# In_Out.net
KiCad netlist of a schematic drawn in Altium Designer
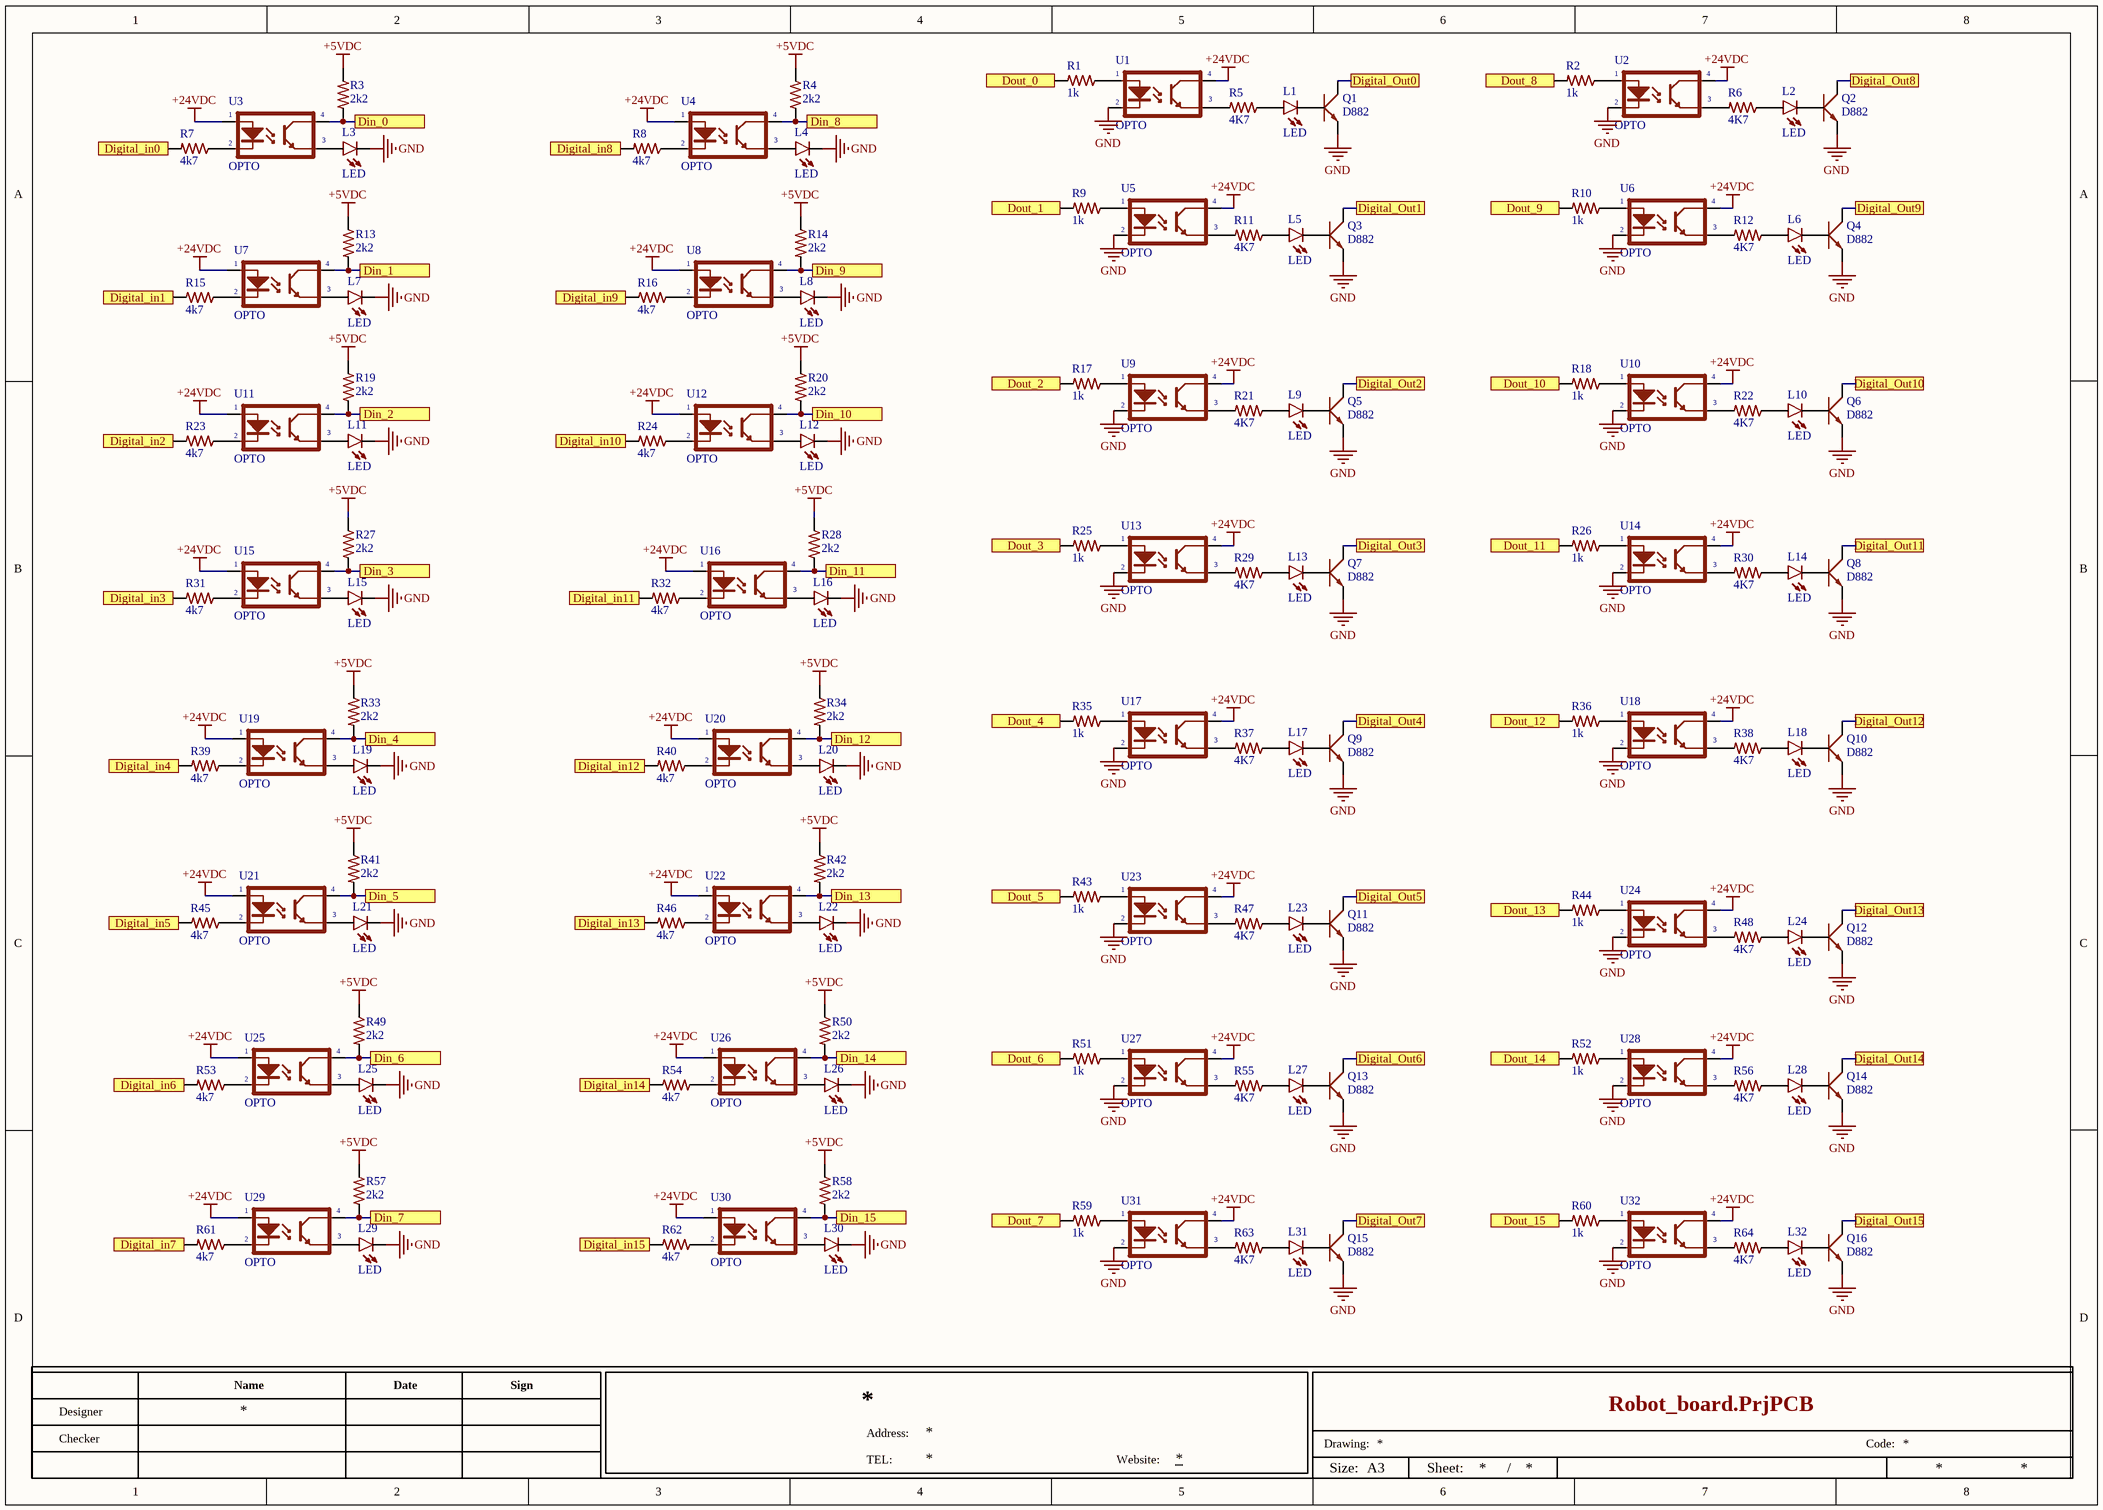
[diagram p0: In_Out.SchDoc]

(export (version "E")
  (design (tool "Eeschema 10.0.6"))
  (components
    (comp (ref "L1")
      (value "LED")
      (footprint "LED_GREEN_SMD_0603")
      (description "Lighting Eminter Diode")
      (libsource (lib "UzumakiIchiro_Library") (part "LED"))
    )
    (comp (ref "L2")
      (value "LED")
      (footprint "LED_GREEN_SMD_0603")
      (description "Lighting Eminter Diode")
      (libsource (lib "UzumakiIchiro_Library") (part "LED"))
    )
    (comp (ref "L3")
      (value "LED")
      (footprint "LED_RED_SMD_0603")
      (description "Lighting Eminter Diode")
      (libsource (lib "UzumakiIchiro_Library") (part "LED"))
    )
    (comp (ref "L4")
      (value "LED")
      (footprint "LED_RED_SMD_0603")
      (description "Lighting Eminter Diode")
      (libsource (lib "UzumakiIchiro_Library") (part "LED"))
    )
    (comp (ref "L5")
      (value "LED")
      (footprint "LED_GREEN_SMD_0603")
      (description "Lighting Eminter Diode")
      (libsource (lib "UzumakiIchiro_Library") (part "LED"))
    )
    (comp (ref "L6")
      (value "LED")
      (footprint "LED_GREEN_SMD_0603")
      (description "Lighting Eminter Diode")
      (libsource (lib "UzumakiIchiro_Library") (part "LED"))
    )
    (comp (ref "L7")
      (value "LED")
      (footprint "LED_RED_SMD_0603")
      (description "Lighting Eminter Diode")
      (libsource (lib "UzumakiIchiro_Library") (part "LED"))
    )
    (comp (ref "L8")
      (value "LED")
      (footprint "LED_RED_SMD_0603")
      (description "Lighting Eminter Diode")
      (libsource (lib "UzumakiIchiro_Library") (part "LED"))
    )
    (comp (ref "L9")
      (value "LED")
      (footprint "LED_GREEN_SMD_0603")
      (description "Lighting Eminter Diode")
      (libsource (lib "UzumakiIchiro_Library") (part "LED"))
    )
    (comp (ref "L10")
      (value "LED")
      (footprint "LED_GREEN_SMD_0603")
      (description "Lighting Eminter Diode")
      (libsource (lib "UzumakiIchiro_Library") (part "LED"))
    )
    (comp (ref "L11")
      (value "LED")
      (footprint "LED_RED_SMD_0603")
      (description "Lighting Eminter Diode")
      (libsource (lib "UzumakiIchiro_Library") (part "LED"))
    )
    (comp (ref "L12")
      (value "LED")
      (footprint "LED_RED_SMD_0603")
      (description "Lighting Eminter Diode")
      (libsource (lib "UzumakiIchiro_Library") (part "LED"))
    )
    (comp (ref "L13")
      (value "LED")
      (footprint "LED_GREEN_SMD_0603")
      (description "Lighting Eminter Diode")
      (libsource (lib "UzumakiIchiro_Library") (part "LED"))
    )
    (comp (ref "L14")
      (value "LED")
      (footprint "LED_GREEN_SMD_0603")
      (description "Lighting Eminter Diode")
      (libsource (lib "UzumakiIchiro_Library") (part "LED"))
    )
    (comp (ref "L15")
      (value "LED")
      (footprint "LED_RED_SMD_0603")
      (description "Lighting Eminter Diode")
      (libsource (lib "UzumakiIchiro_Library") (part "LED"))
    )
    (comp (ref "L16")
      (value "LED")
      (footprint "LED_RED_SMD_0603")
      (description "Lighting Eminter Diode")
      (libsource (lib "UzumakiIchiro_Library") (part "LED"))
    )
    (comp (ref "L17")
      (value "LED")
      (footprint "LED_GREEN_SMD_0603")
      (description "Lighting Eminter Diode")
      (libsource (lib "UzumakiIchiro_Library") (part "LED"))
    )
    (comp (ref "L18")
      (value "LED")
      (footprint "LED_GREEN_SMD_0603")
      (description "Lighting Eminter Diode")
      (libsource (lib "UzumakiIchiro_Library") (part "LED"))
    )
    (comp (ref "L19")
      (value "LED")
      (footprint "LED_RED_SMD_0603")
      (description "Lighting Eminter Diode")
      (libsource (lib "UzumakiIchiro_Library") (part "LED"))
    )
    (comp (ref "L20")
      (value "LED")
      (footprint "LED_RED_SMD_0603")
      (description "Lighting Eminter Diode")
      (libsource (lib "UzumakiIchiro_Library") (part "LED"))
    )
    (comp (ref "L21")
      (value "LED")
      (footprint "LED_RED_SMD_0603")
      (description "Lighting Eminter Diode")
      (libsource (lib "UzumakiIchiro_Library") (part "LED"))
    )
    (comp (ref "L22")
      (value "LED")
      (footprint "LED_RED_SMD_0603")
      (description "Lighting Eminter Diode")
      (libsource (lib "UzumakiIchiro_Library") (part "LED"))
    )
    (comp (ref "L23")
      (value "LED")
      (footprint "LED_GREEN_SMD_0603")
      (description "Lighting Eminter Diode")
      (libsource (lib "UzumakiIchiro_Library") (part "LED"))
    )
    (comp (ref "L24")
      (value "LED")
      (footprint "LED_GREEN_SMD_0603")
      (description "Lighting Eminter Diode")
      (libsource (lib "UzumakiIchiro_Library") (part "LED"))
    )
    (comp (ref "L25")
      (value "LED")
      (footprint "LED_RED_SMD_0603")
      (description "Lighting Eminter Diode")
      (libsource (lib "UzumakiIchiro_Library") (part "LED"))
    )
    (comp (ref "L26")
      (value "LED")
      (footprint "LED_RED_SMD_0603")
      (description "Lighting Eminter Diode")
      (libsource (lib "UzumakiIchiro_Library") (part "LED"))
    )
    (comp (ref "L27")
      (value "LED")
      (footprint "LED_GREEN_SMD_0603")
      (description "Lighting Eminter Diode")
      (libsource (lib "UzumakiIchiro_Library") (part "LED"))
    )
    (comp (ref "L28")
      (value "LED")
      (footprint "LED_GREEN_SMD_0603")
      (description "Lighting Eminter Diode")
      (libsource (lib "UzumakiIchiro_Library") (part "LED"))
    )
    (comp (ref "L29")
      (value "LED")
      (footprint "LED_RED_SMD_0603")
      (description "Lighting Eminter Diode")
      (libsource (lib "UzumakiIchiro_Library") (part "LED"))
    )
    (comp (ref "L30")
      (value "LED")
      (footprint "LED_RED_SMD_0603")
      (description "Lighting Eminter Diode")
      (libsource (lib "UzumakiIchiro_Library") (part "LED"))
    )
    (comp (ref "L31")
      (value "LED")
      (footprint "LED_GREEN_SMD_0603")
      (description "Lighting Eminter Diode")
      (libsource (lib "UzumakiIchiro_Library") (part "LED"))
    )
    (comp (ref "L32")
      (value "LED")
      (footprint "LED_GREEN_SMD_0603")
      (description "Lighting Eminter Diode")
      (libsource (lib "UzumakiIchiro_Library") (part "LED"))
    )
    (comp (ref "Q1")
      (value "D882")
      (footprint "SOT89")
      (libsource (lib "UzumakiIchiro_Library") (part "Tranzitor NPN"))
    )
    (comp (ref "Q2")
      (value "D882")
      (footprint "SOT89")
      (libsource (lib "UzumakiIchiro_Library") (part "Tranzitor NPN"))
    )
    (comp (ref "Q3")
      (value "D882")
      (footprint "SOT89")
      (libsource (lib "UzumakiIchiro_Library") (part "Tranzitor NPN"))
    )
    (comp (ref "Q4")
      (value "D882")
      (footprint "SOT89")
      (libsource (lib "UzumakiIchiro_Library") (part "Tranzitor NPN"))
    )
    (comp (ref "Q5")
      (value "D882")
      (footprint "SOT89")
      (libsource (lib "UzumakiIchiro_Library") (part "Tranzitor NPN"))
    )
    (comp (ref "Q6")
      (value "D882")
      (footprint "SOT89")
      (libsource (lib "UzumakiIchiro_Library") (part "Tranzitor NPN"))
    )
    (comp (ref "Q7")
      (value "D882")
      (footprint "SOT89")
      (libsource (lib "UzumakiIchiro_Library") (part "Tranzitor NPN"))
    )
    (comp (ref "Q8")
      (value "D882")
      (footprint "SOT89")
      (libsource (lib "UzumakiIchiro_Library") (part "Tranzitor NPN"))
    )
    (comp (ref "Q9")
      (value "D882")
      (footprint "SOT89")
      (libsource (lib "UzumakiIchiro_Library") (part "Tranzitor NPN"))
    )
    (comp (ref "Q10")
      (value "D882")
      (footprint "SOT89")
      (libsource (lib "UzumakiIchiro_Library") (part "Tranzitor NPN"))
    )
    (comp (ref "Q11")
      (value "D882")
      (footprint "SOT89")
      (libsource (lib "UzumakiIchiro_Library") (part "Tranzitor NPN"))
    )
    (comp (ref "Q12")
      (value "D882")
      (footprint "SOT89")
      (libsource (lib "UzumakiIchiro_Library") (part "Tranzitor NPN"))
    )
    (comp (ref "Q13")
      (value "D882")
      (footprint "SOT89")
      (libsource (lib "UzumakiIchiro_Library") (part "Tranzitor NPN"))
    )
    (comp (ref "Q14")
      (value "D882")
      (footprint "SOT89")
      (libsource (lib "UzumakiIchiro_Library") (part "Tranzitor NPN"))
    )
    (comp (ref "Q15")
      (value "D882")
      (footprint "SOT89")
      (libsource (lib "UzumakiIchiro_Library") (part "Tranzitor NPN"))
    )
    (comp (ref "Q16")
      (value "D882")
      (footprint "SOT89")
      (libsource (lib "UzumakiIchiro_Library") (part "Tranzitor NPN"))
    )
    (comp (ref "R1")
      (value "1k")
      (footprint "RES_SMD0603")
      (libsource (lib "UzumakiIchiro_Library") (part "Resistor"))
    )
    (comp (ref "R2")
      (value "1k")
      (footprint "RES_SMD0603")
      (libsource (lib "UzumakiIchiro_Library") (part "Resistor"))
    )
    (comp (ref "R3")
      (value "2k2")
      (footprint "RES_SMD0603")
      (libsource (lib "UzumakiIchiro_Library") (part "Resistor"))
    )
    (comp (ref "R4")
      (value "2k2")
      (footprint "RES_SMD0603")
      (libsource (lib "UzumakiIchiro_Library") (part "Resistor"))
    )
    (comp (ref "R5")
      (value "4K7")
      (footprint "RES_SMD0603")
      (libsource (lib "UzumakiIchiro_Library") (part "Resistor"))
    )
    (comp (ref "R6")
      (value "4K7")
      (footprint "RES_SMD0603")
      (libsource (lib "UzumakiIchiro_Library") (part "Resistor"))
    )
    (comp (ref "R7")
      (value "4k7")
      (footprint "RES_SMD0603")
      (libsource (lib "UzumakiIchiro_Library") (part "Resistor"))
    )
    (comp (ref "R8")
      (value "4k7")
      (footprint "RES_SMD0603")
      (libsource (lib "UzumakiIchiro_Library") (part "Resistor"))
    )
    (comp (ref "R9")
      (value "1k")
      (footprint "RES_SMD0603")
      (libsource (lib "UzumakiIchiro_Library") (part "Resistor"))
    )
    (comp (ref "R10")
      (value "1k")
      (footprint "RES_SMD0603")
      (libsource (lib "UzumakiIchiro_Library") (part "Resistor"))
    )
    (comp (ref "R11")
      (value "4K7")
      (footprint "RES_SMD0603")
      (libsource (lib "UzumakiIchiro_Library") (part "Resistor"))
    )
    (comp (ref "R12")
      (value "4K7")
      (footprint "RES_SMD0603")
      (libsource (lib "UzumakiIchiro_Library") (part "Resistor"))
    )
    (comp (ref "R13")
      (value "2k2")
      (footprint "RES_SMD0603")
      (libsource (lib "UzumakiIchiro_Library") (part "Resistor"))
    )
    (comp (ref "R14")
      (value "2k2")
      (footprint "RES_SMD0603")
      (libsource (lib "UzumakiIchiro_Library") (part "Resistor"))
    )
    (comp (ref "R15")
      (value "4k7")
      (footprint "RES_SMD0603")
      (libsource (lib "UzumakiIchiro_Library") (part "Resistor"))
    )
    (comp (ref "R16")
      (value "4k7")
      (footprint "RES_SMD0603")
      (libsource (lib "UzumakiIchiro_Library") (part "Resistor"))
    )
    (comp (ref "R17")
      (value "1k")
      (footprint "RES_SMD0603")
      (libsource (lib "UzumakiIchiro_Library") (part "Resistor"))
    )
    (comp (ref "R18")
      (value "1k")
      (footprint "RES_SMD0603")
      (libsource (lib "UzumakiIchiro_Library") (part "Resistor"))
    )
    (comp (ref "R19")
      (value "2k2")
      (footprint "RES_SMD0603")
      (libsource (lib "UzumakiIchiro_Library") (part "Resistor"))
    )
    (comp (ref "R20")
      (value "2k2")
      (footprint "RES_SMD0603")
      (libsource (lib "UzumakiIchiro_Library") (part "Resistor"))
    )
    (comp (ref "R21")
      (value "4K7")
      (footprint "RES_SMD0603")
      (libsource (lib "UzumakiIchiro_Library") (part "Resistor"))
    )
    (comp (ref "R22")
      (value "4K7")
      (footprint "RES_SMD0603")
      (libsource (lib "UzumakiIchiro_Library") (part "Resistor"))
    )
    (comp (ref "R23")
      (value "4k7")
      (footprint "RES_SMD0603")
      (libsource (lib "UzumakiIchiro_Library") (part "Resistor"))
    )
    (comp (ref "R24")
      (value "4k7")
      (footprint "RES_SMD0603")
      (libsource (lib "UzumakiIchiro_Library") (part "Resistor"))
    )
    (comp (ref "R25")
      (value "1k")
      (footprint "RES_SMD0603")
      (libsource (lib "UzumakiIchiro_Library") (part "Resistor"))
    )
    (comp (ref "R26")
      (value "1k")
      (footprint "RES_SMD0603")
      (libsource (lib "UzumakiIchiro_Library") (part "Resistor"))
    )
    (comp (ref "R27")
      (value "2k2")
      (footprint "RES_SMD0603")
      (libsource (lib "UzumakiIchiro_Library") (part "Resistor"))
    )
    (comp (ref "R28")
      (value "2k2")
      (footprint "RES_SMD0603")
      (libsource (lib "UzumakiIchiro_Library") (part "Resistor"))
    )
    (comp (ref "R29")
      (value "4K7")
      (footprint "RES_SMD0603")
      (libsource (lib "UzumakiIchiro_Library") (part "Resistor"))
    )
    (comp (ref "R30")
      (value "4K7")
      (footprint "RES_SMD0603")
      (libsource (lib "UzumakiIchiro_Library") (part "Resistor"))
    )
    (comp (ref "R31")
      (value "4k7")
      (footprint "RES_SMD0603")
      (libsource (lib "UzumakiIchiro_Library") (part "Resistor"))
    )
    (comp (ref "R32")
      (value "4k7")
      (footprint "RES_SMD0603")
      (libsource (lib "UzumakiIchiro_Library") (part "Resistor"))
    )
    (comp (ref "R33")
      (value "2k2")
      (footprint "RES_SMD0603")
      (libsource (lib "UzumakiIchiro_Library") (part "Resistor"))
    )
    (comp (ref "R34")
      (value "2k2")
      (footprint "RES_SMD0603")
      (libsource (lib "UzumakiIchiro_Library") (part "Resistor"))
    )
    (comp (ref "R35")
      (value "1k")
      (footprint "RES_SMD0603")
      (libsource (lib "UzumakiIchiro_Library") (part "Resistor"))
    )
    (comp (ref "R36")
      (value "1k")
      (footprint "RES_SMD0603")
      (libsource (lib "UzumakiIchiro_Library") (part "Resistor"))
    )
    (comp (ref "R37")
      (value "4K7")
      (footprint "RES_SMD0603")
      (libsource (lib "UzumakiIchiro_Library") (part "Resistor"))
    )
    (comp (ref "R38")
      (value "4K7")
      (footprint "RES_SMD0603")
      (libsource (lib "UzumakiIchiro_Library") (part "Resistor"))
    )
    (comp (ref "R39")
      (value "4k7")
      (footprint "RES_SMD0603")
      (libsource (lib "UzumakiIchiro_Library") (part "Resistor"))
    )
    (comp (ref "R40")
      (value "4k7")
      (footprint "RES_SMD0603")
      (libsource (lib "UzumakiIchiro_Library") (part "Resistor"))
    )
    (comp (ref "R41")
      (value "2k2")
      (footprint "RES_SMD0603")
      (libsource (lib "UzumakiIchiro_Library") (part "Resistor"))
    )
    (comp (ref "R42")
      (value "2k2")
      (footprint "RES_SMD0603")
      (libsource (lib "UzumakiIchiro_Library") (part "Resistor"))
    )
    (comp (ref "R43")
      (value "1k")
      (footprint "RES_SMD0603")
      (libsource (lib "UzumakiIchiro_Library") (part "Resistor"))
    )
    (comp (ref "R44")
      (value "1k")
      (footprint "RES_SMD0603")
      (libsource (lib "UzumakiIchiro_Library") (part "Resistor"))
    )
    (comp (ref "R45")
      (value "4k7")
      (footprint "RES_SMD0603")
      (libsource (lib "UzumakiIchiro_Library") (part "Resistor"))
    )
    (comp (ref "R46")
      (value "4k7")
      (footprint "RES_SMD0603")
      (libsource (lib "UzumakiIchiro_Library") (part "Resistor"))
    )
    (comp (ref "R47")
      (value "4K7")
      (footprint "RES_SMD0603")
      (libsource (lib "UzumakiIchiro_Library") (part "Resistor"))
    )
    (comp (ref "R48")
      (value "4K7")
      (footprint "RES_SMD0603")
      (libsource (lib "UzumakiIchiro_Library") (part "Resistor"))
    )
    (comp (ref "R49")
      (value "2k2")
      (footprint "RES_SMD0603")
      (libsource (lib "UzumakiIchiro_Library") (part "Resistor"))
    )
    (comp (ref "R50")
      (value "2k2")
      (footprint "RES_SMD0603")
      (libsource (lib "UzumakiIchiro_Library") (part "Resistor"))
    )
    (comp (ref "R51")
      (value "1k")
      (footprint "RES_SMD0603")
      (libsource (lib "UzumakiIchiro_Library") (part "Resistor"))
    )
    (comp (ref "R52")
      (value "1k")
      (footprint "RES_SMD0603")
      (libsource (lib "UzumakiIchiro_Library") (part "Resistor"))
    )
    (comp (ref "R53")
      (value "4k7")
      (footprint "RES_SMD0603")
      (libsource (lib "UzumakiIchiro_Library") (part "Resistor"))
    )
    (comp (ref "R54")
      (value "4k7")
      (footprint "RES_SMD0603")
      (libsource (lib "UzumakiIchiro_Library") (part "Resistor"))
    )
    (comp (ref "R55")
      (value "4K7")
      (footprint "RES_SMD0603")
      (libsource (lib "UzumakiIchiro_Library") (part "Resistor"))
    )
    (comp (ref "R56")
      (value "4K7")
      (footprint "RES_SMD0603")
      (libsource (lib "UzumakiIchiro_Library") (part "Resistor"))
    )
    (comp (ref "R57")
      (value "2k2")
      (footprint "RES_SMD0603")
      (libsource (lib "UzumakiIchiro_Library") (part "Resistor"))
    )
    (comp (ref "R58")
      (value "2k2")
      (footprint "RES_SMD0603")
      (libsource (lib "UzumakiIchiro_Library") (part "Resistor"))
    )
    (comp (ref "R59")
      (value "1k")
      (footprint "RES_SMD0603")
      (libsource (lib "UzumakiIchiro_Library") (part "Resistor"))
    )
    (comp (ref "R60")
      (value "1k")
      (footprint "RES_SMD0603")
      (libsource (lib "UzumakiIchiro_Library") (part "Resistor"))
    )
    (comp (ref "R61")
      (value "4k7")
      (footprint "RES_SMD0603")
      (libsource (lib "UzumakiIchiro_Library") (part "Resistor"))
    )
    (comp (ref "R62")
      (value "4k7")
      (footprint "RES_SMD0603")
      (libsource (lib "UzumakiIchiro_Library") (part "Resistor"))
    )
    (comp (ref "R63")
      (value "4K7")
      (footprint "RES_SMD0603")
      (libsource (lib "UzumakiIchiro_Library") (part "Resistor"))
    )
    (comp (ref "R64")
      (value "4K7")
      (footprint "RES_SMD0603")
      (libsource (lib "UzumakiIchiro_Library") (part "Resistor"))
    )
    (comp (ref "U1")
      (value "OPTO")
      (footprint "SOP4")
      (libsource (lib "UzumakiIchiro_Library") (part "OPTO"))
    )
    (comp (ref "U2")
      (value "OPTO")
      (footprint "SOP4")
      (libsource (lib "UzumakiIchiro_Library") (part "OPTO"))
    )
    (comp (ref "U3")
      (value "OPTO")
      (footprint "SOP4")
      (libsource (lib "UzumakiIchiro_Library") (part "OPTO"))
    )
    (comp (ref "U4")
      (value "OPTO")
      (footprint "SOP4")
      (libsource (lib "UzumakiIchiro_Library") (part "OPTO"))
    )
    (comp (ref "U5")
      (value "OPTO")
      (footprint "SOP4")
      (libsource (lib "UzumakiIchiro_Library") (part "OPTO"))
    )
    (comp (ref "U6")
      (value "OPTO")
      (footprint "SOP4")
      (libsource (lib "UzumakiIchiro_Library") (part "OPTO"))
    )
    (comp (ref "U7")
      (value "OPTO")
      (footprint "SOP4")
      (libsource (lib "UzumakiIchiro_Library") (part "OPTO"))
    )
    (comp (ref "U8")
      (value "OPTO")
      (footprint "SOP4")
      (libsource (lib "UzumakiIchiro_Library") (part "OPTO"))
    )
    (comp (ref "U9")
      (value "OPTO")
      (footprint "SOP4")
      (libsource (lib "UzumakiIchiro_Library") (part "OPTO"))
    )
    (comp (ref "U10")
      (value "OPTO")
      (footprint "SOP4")
      (libsource (lib "UzumakiIchiro_Library") (part "OPTO"))
    )
    (comp (ref "U11")
      (value "OPTO")
      (footprint "SOP4")
      (libsource (lib "UzumakiIchiro_Library") (part "OPTO"))
    )
    (comp (ref "U12")
      (value "OPTO")
      (footprint "SOP4")
      (libsource (lib "UzumakiIchiro_Library") (part "OPTO"))
    )
    (comp (ref "U13")
      (value "OPTO")
      (footprint "SOP4")
      (libsource (lib "UzumakiIchiro_Library") (part "OPTO"))
    )
    (comp (ref "U14")
      (value "OPTO")
      (footprint "SOP4")
      (libsource (lib "UzumakiIchiro_Library") (part "OPTO"))
    )
    (comp (ref "U15")
      (value "OPTO")
      (footprint "SOP4")
      (libsource (lib "UzumakiIchiro_Library") (part "OPTO"))
    )
    (comp (ref "U16")
      (value "OPTO")
      (footprint "SOP4")
      (libsource (lib "UzumakiIchiro_Library") (part "OPTO"))
    )
    (comp (ref "U17")
      (value "OPTO")
      (footprint "SOP4")
      (libsource (lib "UzumakiIchiro_Library") (part "OPTO"))
    )
    (comp (ref "U18")
      (value "OPTO")
      (footprint "SOP4")
      (libsource (lib "UzumakiIchiro_Library") (part "OPTO"))
    )
    (comp (ref "U19")
      (value "OPTO")
      (footprint "SOP4")
      (libsource (lib "UzumakiIchiro_Library") (part "OPTO"))
    )
    (comp (ref "U20")
      (value "OPTO")
      (footprint "SOP4")
      (libsource (lib "UzumakiIchiro_Library") (part "OPTO"))
    )
    (comp (ref "U21")
      (value "OPTO")
      (footprint "SOP4")
      (libsource (lib "UzumakiIchiro_Library") (part "OPTO"))
    )
    (comp (ref "U22")
      (value "OPTO")
      (footprint "SOP4")
      (libsource (lib "UzumakiIchiro_Library") (part "OPTO"))
    )
    (comp (ref "U23")
      (value "OPTO")
      (footprint "SOP4")
      (libsource (lib "UzumakiIchiro_Library") (part "OPTO"))
    )
    (comp (ref "U24")
      (value "OPTO")
      (footprint "SOP4")
      (libsource (lib "UzumakiIchiro_Library") (part "OPTO"))
    )
    (comp (ref "U25")
      (value "OPTO")
      (footprint "SOP4")
      (libsource (lib "UzumakiIchiro_Library") (part "OPTO"))
    )
    (comp (ref "U26")
      (value "OPTO")
      (footprint "SOP4")
      (libsource (lib "UzumakiIchiro_Library") (part "OPTO"))
    )
    (comp (ref "U27")
      (value "OPTO")
      (footprint "SOP4")
      (libsource (lib "UzumakiIchiro_Library") (part "OPTO"))
    )
    (comp (ref "U28")
      (value "OPTO")
      (footprint "SOP4")
      (libsource (lib "UzumakiIchiro_Library") (part "OPTO"))
    )
    (comp (ref "U29")
      (value "OPTO")
      (footprint "SOP4")
      (libsource (lib "UzumakiIchiro_Library") (part "OPTO"))
    )
    (comp (ref "U30")
      (value "OPTO")
      (footprint "SOP4")
      (libsource (lib "UzumakiIchiro_Library") (part "OPTO"))
    )
    (comp (ref "U31")
      (value "OPTO")
      (footprint "SOP4")
      (libsource (lib "UzumakiIchiro_Library") (part "OPTO"))
    )
    (comp (ref "U32")
      (value "OPTO")
      (footprint "SOP4")
      (libsource (lib "UzumakiIchiro_Library") (part "OPTO"))
    )
  )
  (nets
    (net (code "1") (name "+5VDC") (class "Default")
      (node (ref "R13") (pin "1") (pinfunction "1_1") (pintype "passive"))
      (node (ref "R14") (pin "1") (pinfunction "1_1") (pintype "passive"))
      (node (ref "R19") (pin "1") (pinfunction "1_1") (pintype "passive"))
      (node (ref "R20") (pin "1") (pinfunction "1_1") (pintype "passive"))
      (node (ref "R27") (pin "1") (pinfunction "1_1") (pintype "passive"))
      (node (ref "R28") (pin "1") (pinfunction "1_1") (pintype "passive"))
      (node (ref "R3") (pin "1") (pinfunction "1_1") (pintype "passive"))
      (node (ref "R33") (pin "1") (pinfunction "1_1") (pintype "passive"))
      (node (ref "R34") (pin "1") (pinfunction "1_1") (pintype "passive"))
      (node (ref "R4") (pin "1") (pinfunction "1_1") (pintype "passive"))
      (node (ref "R41") (pin "1") (pinfunction "1_1") (pintype "passive"))
      (node (ref "R42") (pin "1") (pinfunction "1_1") (pintype "passive"))
      (node (ref "R49") (pin "1") (pinfunction "1_1") (pintype "passive"))
      (node (ref "R50") (pin "1") (pinfunction "1_1") (pintype "passive"))
      (node (ref "R57") (pin "1") (pinfunction "1_1") (pintype "passive"))
      (node (ref "R58") (pin "1") (pinfunction "1_1") (pintype "passive"))
    )
    (net (code "2") (name "+24VDC") (class "Default")
      (node (ref "U1") (pin "4") (pinfunction "C_4") (pintype "passive"))
      (node (ref "U10") (pin "4") (pinfunction "C_4") (pintype "passive"))
      (node (ref "U11") (pin "1") (pinfunction "A_1") (pintype "passive"))
      (node (ref "U12") (pin "1") (pinfunction "A_1") (pintype "passive"))
      (node (ref "U13") (pin "4") (pinfunction "C_4") (pintype "passive"))
      (node (ref "U14") (pin "4") (pinfunction "C_4") (pintype "passive"))
      (node (ref "U15") (pin "1") (pinfunction "A_1") (pintype "passive"))
      (node (ref "U16") (pin "1") (pinfunction "A_1") (pintype "passive"))
      (node (ref "U17") (pin "4") (pinfunction "C_4") (pintype "passive"))
      (node (ref "U18") (pin "4") (pinfunction "C_4") (pintype "passive"))
      (node (ref "U19") (pin "1") (pinfunction "A_1") (pintype "passive"))
      (node (ref "U2") (pin "4") (pinfunction "C_4") (pintype "passive"))
      (node (ref "U20") (pin "1") (pinfunction "A_1") (pintype "passive"))
      (node (ref "U21") (pin "1") (pinfunction "A_1") (pintype "passive"))
      (node (ref "U22") (pin "1") (pinfunction "A_1") (pintype "passive"))
      (node (ref "U23") (pin "4") (pinfunction "C_4") (pintype "passive"))
      (node (ref "U24") (pin "4") (pinfunction "C_4") (pintype "passive"))
      (node (ref "U25") (pin "1") (pinfunction "A_1") (pintype "passive"))
      (node (ref "U26") (pin "1") (pinfunction "A_1") (pintype "passive"))
      (node (ref "U27") (pin "4") (pinfunction "C_4") (pintype "passive"))
      (node (ref "U28") (pin "4") (pinfunction "C_4") (pintype "passive"))
      (node (ref "U29") (pin "1") (pinfunction "A_1") (pintype "passive"))
      (node (ref "U3") (pin "1") (pinfunction "A_1") (pintype "passive"))
      (node (ref "U30") (pin "1") (pinfunction "A_1") (pintype "passive"))
      (node (ref "U31") (pin "4") (pinfunction "C_4") (pintype "passive"))
      (node (ref "U32") (pin "4") (pinfunction "C_4") (pintype "passive"))
      (node (ref "U4") (pin "1") (pinfunction "A_1") (pintype "passive"))
      (node (ref "U5") (pin "4") (pinfunction "C_4") (pintype "passive"))
      (node (ref "U6") (pin "4") (pinfunction "C_4") (pintype "passive"))
      (node (ref "U7") (pin "1") (pinfunction "A_1") (pintype "passive"))
      (node (ref "U8") (pin "1") (pinfunction "A_1") (pintype "passive"))
      (node (ref "U9") (pin "4") (pinfunction "C_4") (pintype "passive"))
    )
    (net (code "3") (name "/Digital_Out0") (class "Default")
      (node (ref "Q1") (pin "3") (pinfunction "COLLECTOR_3") (pintype "passive"))
    )
    (net (code "4") (name "/Digital_Out1") (class "Default")
      (node (ref "Q3") (pin "3") (pinfunction "COLLECTOR_3") (pintype "passive"))
    )
    (net (code "5") (name "/Digital_Out2") (class "Default")
      (node (ref "Q5") (pin "3") (pinfunction "COLLECTOR_3") (pintype "passive"))
    )
    (net (code "6") (name "/Digital_Out3") (class "Default")
      (node (ref "Q7") (pin "3") (pinfunction "COLLECTOR_3") (pintype "passive"))
    )
    (net (code "7") (name "/Digital_Out4") (class "Default")
      (node (ref "Q9") (pin "3") (pinfunction "COLLECTOR_3") (pintype "passive"))
    )
    (net (code "8") (name "/Digital_Out5") (class "Default")
      (node (ref "Q11") (pin "3") (pinfunction "COLLECTOR_3") (pintype "passive"))
    )
    (net (code "9") (name "/Digital_Out6") (class "Default")
      (node (ref "Q13") (pin "3") (pinfunction "COLLECTOR_3") (pintype "passive"))
    )
    (net (code "10") (name "/Digital_Out7") (class "Default")
      (node (ref "Q15") (pin "3") (pinfunction "COLLECTOR_3") (pintype "passive"))
    )
    (net (code "11") (name "/Digital_Out8") (class "Default")
      (node (ref "Q2") (pin "3") (pinfunction "COLLECTOR_3") (pintype "passive"))
    )
    (net (code "12") (name "/Digital_Out9") (class "Default")
      (node (ref "Q4") (pin "3") (pinfunction "COLLECTOR_3") (pintype "passive"))
    )
    (net (code "13") (name "/Digital_Out10") (class "Default")
      (node (ref "Q6") (pin "3") (pinfunction "COLLECTOR_3") (pintype "passive"))
    )
    (net (code "14") (name "/Digital_Out11") (class "Default")
      (node (ref "Q8") (pin "3") (pinfunction "COLLECTOR_3") (pintype "passive"))
    )
    (net (code "15") (name "/Digital_Out12") (class "Default")
      (node (ref "Q10") (pin "3") (pinfunction "COLLECTOR_3") (pintype "passive"))
    )
    (net (code "16") (name "/Digital_Out13") (class "Default")
      (node (ref "Q12") (pin "3") (pinfunction "COLLECTOR_3") (pintype "passive"))
    )
    (net (code "17") (name "/Digital_Out14") (class "Default")
      (node (ref "Q14") (pin "3") (pinfunction "COLLECTOR_3") (pintype "passive"))
    )
    (net (code "18") (name "/Digital_Out15") (class "Default")
      (node (ref "Q16") (pin "3") (pinfunction "COLLECTOR_3") (pintype "passive"))
    )
    (net (code "19") (name "/Digital_in0") (class "Default")
      (node (ref "R7") (pin "2") (pinfunction "2_2") (pintype "passive"))
    )
    (net (code "20") (name "/Digital_in1") (class "Default")
      (node (ref "R15") (pin "2") (pinfunction "2_2") (pintype "passive"))
    )
    (net (code "21") (name "/Digital_in2") (class "Default")
      (node (ref "R23") (pin "2") (pinfunction "2_2") (pintype "passive"))
    )
    (net (code "22") (name "/Digital_in3") (class "Default")
      (node (ref "R31") (pin "2") (pinfunction "2_2") (pintype "passive"))
    )
    (net (code "23") (name "/Digital_in4") (class "Default")
      (node (ref "R39") (pin "2") (pinfunction "2_2") (pintype "passive"))
    )
    (net (code "24") (name "/Digital_in5") (class "Default")
      (node (ref "R45") (pin "2") (pinfunction "2_2") (pintype "passive"))
    )
    (net (code "25") (name "/Digital_in6") (class "Default")
      (node (ref "R53") (pin "2") (pinfunction "2_2") (pintype "passive"))
    )
    (net (code "26") (name "/Digital_in7") (class "Default")
      (node (ref "R61") (pin "2") (pinfunction "2_2") (pintype "passive"))
    )
    (net (code "27") (name "/Digital_in8") (class "Default")
      (node (ref "R8") (pin "2") (pinfunction "2_2") (pintype "passive"))
    )
    (net (code "28") (name "/Digital_in9") (class "Default")
      (node (ref "R16") (pin "2") (pinfunction "2_2") (pintype "passive"))
    )
    (net (code "29") (name "/Digital_in10") (class "Default")
      (node (ref "R24") (pin "2") (pinfunction "2_2") (pintype "passive"))
    )
    (net (code "30") (name "/Digital_in11") (class "Default")
      (node (ref "R32") (pin "2") (pinfunction "2_2") (pintype "passive"))
    )
    (net (code "31") (name "/Digital_in12") (class "Default")
      (node (ref "R40") (pin "2") (pinfunction "2_2") (pintype "passive"))
    )
    (net (code "32") (name "/Digital_in13") (class "Default")
      (node (ref "R46") (pin "2") (pinfunction "2_2") (pintype "passive"))
    )
    (net (code "33") (name "/Digital_in14") (class "Default")
      (node (ref "R54") (pin "2") (pinfunction "2_2") (pintype "passive"))
    )
    (net (code "34") (name "/Digital_in15") (class "Default")
      (node (ref "R62") (pin "2") (pinfunction "2_2") (pintype "passive"))
    )
    (net (code "35") (name "/Din_0") (class "Default")
      (node (ref "R3") (pin "2") (pinfunction "2_2") (pintype "passive"))
      (node (ref "U3") (pin "4") (pinfunction "C_4") (pintype "passive"))
    )
    (net (code "36") (name "/Din_1") (class "Default")
      (node (ref "R13") (pin "2") (pinfunction "2_2") (pintype "passive"))
      (node (ref "U7") (pin "4") (pinfunction "C_4") (pintype "passive"))
    )
    (net (code "37") (name "/Din_2") (class "Default")
      (node (ref "R19") (pin "2") (pinfunction "2_2") (pintype "passive"))
      (node (ref "U11") (pin "4") (pinfunction "C_4") (pintype "passive"))
    )
    (net (code "38") (name "/Din_3") (class "Default")
      (node (ref "R27") (pin "2") (pinfunction "2_2") (pintype "passive"))
      (node (ref "U15") (pin "4") (pinfunction "C_4") (pintype "passive"))
    )
    (net (code "39") (name "/Din_4") (class "Default")
      (node (ref "R33") (pin "2") (pinfunction "2_2") (pintype "passive"))
      (node (ref "U19") (pin "4") (pinfunction "C_4") (pintype "passive"))
    )
    (net (code "40") (name "/Din_5") (class "Default")
      (node (ref "R41") (pin "2") (pinfunction "2_2") (pintype "passive"))
      (node (ref "U21") (pin "4") (pinfunction "C_4") (pintype "passive"))
    )
    (net (code "41") (name "/Din_6") (class "Default")
      (node (ref "R49") (pin "2") (pinfunction "2_2") (pintype "passive"))
      (node (ref "U25") (pin "4") (pinfunction "C_4") (pintype "passive"))
    )
    (net (code "42") (name "/Din_7") (class "Default")
      (node (ref "R57") (pin "2") (pinfunction "2_2") (pintype "passive"))
      (node (ref "U29") (pin "4") (pinfunction "C_4") (pintype "passive"))
    )
    (net (code "43") (name "/Din_8") (class "Default")
      (node (ref "R4") (pin "2") (pinfunction "2_2") (pintype "passive"))
      (node (ref "U4") (pin "4") (pinfunction "C_4") (pintype "passive"))
    )
    (net (code "44") (name "/Din_9") (class "Default")
      (node (ref "R14") (pin "2") (pinfunction "2_2") (pintype "passive"))
      (node (ref "U8") (pin "4") (pinfunction "C_4") (pintype "passive"))
    )
    (net (code "45") (name "/Din_10") (class "Default")
      (node (ref "R20") (pin "2") (pinfunction "2_2") (pintype "passive"))
      (node (ref "U12") (pin "4") (pinfunction "C_4") (pintype "passive"))
    )
    (net (code "46") (name "/Din_11") (class "Default")
      (node (ref "R28") (pin "2") (pinfunction "2_2") (pintype "passive"))
      (node (ref "U16") (pin "4") (pinfunction "C_4") (pintype "passive"))
    )
    (net (code "47") (name "/Din_12") (class "Default")
      (node (ref "R34") (pin "2") (pinfunction "2_2") (pintype "passive"))
      (node (ref "U20") (pin "4") (pinfunction "C_4") (pintype "passive"))
    )
    (net (code "48") (name "/Din_13") (class "Default")
      (node (ref "R42") (pin "2") (pinfunction "2_2") (pintype "passive"))
      (node (ref "U22") (pin "4") (pinfunction "C_4") (pintype "passive"))
    )
    (net (code "49") (name "/Din_14") (class "Default")
      (node (ref "R50") (pin "2") (pinfunction "2_2") (pintype "passive"))
      (node (ref "U26") (pin "4") (pinfunction "C_4") (pintype "passive"))
    )
    (net (code "50") (name "/Din_15") (class "Default")
      (node (ref "R58") (pin "2") (pinfunction "2_2") (pintype "passive"))
      (node (ref "U30") (pin "4") (pinfunction "C_4") (pintype "passive"))
    )
    (net (code "51") (name "/Dout_0") (class "Default")
      (node (ref "R1") (pin "2") (pinfunction "2_2") (pintype "passive"))
    )
    (net (code "52") (name "/Dout_1") (class "Default")
      (node (ref "R9") (pin "2") (pinfunction "2_2") (pintype "passive"))
    )
    (net (code "53") (name "/Dout_2") (class "Default")
      (node (ref "R17") (pin "2") (pinfunction "2_2") (pintype "passive"))
    )
    (net (code "54") (name "/Dout_3") (class "Default")
      (node (ref "R25") (pin "2") (pinfunction "2_2") (pintype "passive"))
    )
    (net (code "55") (name "/Dout_4") (class "Default")
      (node (ref "R35") (pin "2") (pinfunction "2_2") (pintype "passive"))
    )
    (net (code "56") (name "/Dout_5") (class "Default")
      (node (ref "R43") (pin "2") (pinfunction "2_2") (pintype "passive"))
    )
    (net (code "57") (name "/Dout_6") (class "Default")
      (node (ref "R51") (pin "2") (pinfunction "2_2") (pintype "passive"))
    )
    (net (code "58") (name "/Dout_7") (class "Default")
      (node (ref "R59") (pin "2") (pinfunction "2_2") (pintype "passive"))
    )
    (net (code "59") (name "/Dout_8") (class "Default")
      (node (ref "R2") (pin "2") (pinfunction "2_2") (pintype "passive"))
    )
    (net (code "60") (name "/Dout_9") (class "Default")
      (node (ref "R10") (pin "2") (pinfunction "2_2") (pintype "passive"))
    )
    (net (code "61") (name "/Dout_10") (class "Default")
      (node (ref "R18") (pin "2") (pinfunction "2_2") (pintype "passive"))
    )
    (net (code "62") (name "/Dout_11") (class "Default")
      (node (ref "R26") (pin "2") (pinfunction "2_2") (pintype "passive"))
    )
    (net (code "63") (name "/Dout_12") (class "Default")
      (node (ref "R36") (pin "2") (pinfunction "2_2") (pintype "passive"))
    )
    (net (code "64") (name "/Dout_13") (class "Default")
      (node (ref "R44") (pin "2") (pinfunction "2_2") (pintype "passive"))
    )
    (net (code "65") (name "/Dout_14") (class "Default")
      (node (ref "R52") (pin "2") (pinfunction "2_2") (pintype "passive"))
    )
    (net (code "66") (name "/Dout_15") (class "Default")
      (node (ref "R60") (pin "2") (pinfunction "2_2") (pintype "passive"))
    )
    (net (code "67") (name "GND") (class "Default")
      (node (ref "L11") (pin "2") (pinfunction "POS_2") (pintype "passive"))
      (node (ref "L12") (pin "2") (pinfunction "POS_2") (pintype "passive"))
      (node (ref "L15") (pin "2") (pinfunction "POS_2") (pintype "passive"))
      (node (ref "L16") (pin "2") (pinfunction "POS_2") (pintype "passive"))
      (node (ref "L19") (pin "2") (pinfunction "POS_2") (pintype "passive"))
      (node (ref "L20") (pin "2") (pinfunction "POS_2") (pintype "passive"))
      (node (ref "L21") (pin "2") (pinfunction "POS_2") (pintype "passive"))
      (node (ref "L22") (pin "2") (pinfunction "POS_2") (pintype "passive"))
      (node (ref "L25") (pin "2") (pinfunction "POS_2") (pintype "passive"))
      (node (ref "L26") (pin "2") (pinfunction "POS_2") (pintype "passive"))
      (node (ref "L29") (pin "2") (pinfunction "POS_2") (pintype "passive"))
      (node (ref "L3") (pin "2") (pinfunction "POS_2") (pintype "passive"))
      (node (ref "L30") (pin "2") (pinfunction "POS_2") (pintype "passive"))
      (node (ref "L4") (pin "2") (pinfunction "POS_2") (pintype "passive"))
      (node (ref "L7") (pin "2") (pinfunction "POS_2") (pintype "passive"))
      (node (ref "L8") (pin "2") (pinfunction "POS_2") (pintype "passive"))
      (node (ref "Q1") (pin "2") (pinfunction "EMITTER_2") (pintype "passive"))
      (node (ref "Q10") (pin "2") (pinfunction "EMITTER_2") (pintype "passive"))
      (node (ref "Q11") (pin "2") (pinfunction "EMITTER_2") (pintype "passive"))
      (node (ref "Q12") (pin "2") (pinfunction "EMITTER_2") (pintype "passive"))
      (node (ref "Q13") (pin "2") (pinfunction "EMITTER_2") (pintype "passive"))
      (node (ref "Q14") (pin "2") (pinfunction "EMITTER_2") (pintype "passive"))
      (node (ref "Q15") (pin "2") (pinfunction "EMITTER_2") (pintype "passive"))
      (node (ref "Q16") (pin "2") (pinfunction "EMITTER_2") (pintype "passive"))
      (node (ref "Q2") (pin "2") (pinfunction "EMITTER_2") (pintype "passive"))
      (node (ref "Q3") (pin "2") (pinfunction "EMITTER_2") (pintype "passive"))
      (node (ref "Q4") (pin "2") (pinfunction "EMITTER_2") (pintype "passive"))
      (node (ref "Q5") (pin "2") (pinfunction "EMITTER_2") (pintype "passive"))
      (node (ref "Q6") (pin "2") (pinfunction "EMITTER_2") (pintype "passive"))
      (node (ref "Q7") (pin "2") (pinfunction "EMITTER_2") (pintype "passive"))
      (node (ref "Q8") (pin "2") (pinfunction "EMITTER_2") (pintype "passive"))
      (node (ref "Q9") (pin "2") (pinfunction "EMITTER_2") (pintype "passive"))
      (node (ref "U1") (pin "2") (pinfunction "K_2") (pintype "passive"))
      (node (ref "U10") (pin "2") (pinfunction "K_2") (pintype "passive"))
      (node (ref "U13") (pin "2") (pinfunction "K_2") (pintype "passive"))
      (node (ref "U14") (pin "2") (pinfunction "K_2") (pintype "passive"))
      (node (ref "U17") (pin "2") (pinfunction "K_2") (pintype "passive"))
      (node (ref "U18") (pin "2") (pinfunction "K_2") (pintype "passive"))
      (node (ref "U2") (pin "2") (pinfunction "K_2") (pintype "passive"))
      (node (ref "U23") (pin "2") (pinfunction "K_2") (pintype "passive"))
      (node (ref "U24") (pin "2") (pinfunction "K_2") (pintype "passive"))
      (node (ref "U27") (pin "2") (pinfunction "K_2") (pintype "passive"))
      (node (ref "U28") (pin "2") (pinfunction "K_2") (pintype "passive"))
      (node (ref "U31") (pin "2") (pinfunction "K_2") (pintype "passive"))
      (node (ref "U32") (pin "2") (pinfunction "K_2") (pintype "passive"))
      (node (ref "U5") (pin "2") (pinfunction "K_2") (pintype "passive"))
      (node (ref "U6") (pin "2") (pinfunction "K_2") (pintype "passive"))
      (node (ref "U9") (pin "2") (pinfunction "K_2") (pintype "passive"))
    )
    (net (code "68") (name "Net-(L1-NEG)") (class "Default")
      (node (ref "L1") (pin "1") (pinfunction "NEG_1") (pintype "passive"))
      (node (ref "R5") (pin "1") (pinfunction "1_1") (pintype "passive"))
    )
    (net (code "69") (name "Net-(L1-POS)") (class "Default")
      (node (ref "L1") (pin "2") (pinfunction "POS_2") (pintype "passive"))
      (node (ref "Q1") (pin "1") (pinfunction "BASE_1") (pintype "passive"))
    )
    (net (code "70") (name "Net-(L2-NEG)") (class "Default")
      (node (ref "L2") (pin "1") (pinfunction "NEG_1") (pintype "passive"))
      (node (ref "R6") (pin "1") (pinfunction "1_1") (pintype "passive"))
    )
    (net (code "71") (name "Net-(L2-POS)") (class "Default")
      (node (ref "L2") (pin "2") (pinfunction "POS_2") (pintype "passive"))
      (node (ref "Q2") (pin "1") (pinfunction "BASE_1") (pintype "passive"))
    )
    (net (code "72") (name "Net-(L3-NEG)") (class "Default")
      (node (ref "L3") (pin "1") (pinfunction "NEG_1") (pintype "passive"))
      (node (ref "U3") (pin "3") (pinfunction "E_3") (pintype "passive"))
    )
    (net (code "73") (name "Net-(L4-NEG)") (class "Default")
      (node (ref "L4") (pin "1") (pinfunction "NEG_1") (pintype "passive"))
      (node (ref "U4") (pin "3") (pinfunction "E_3") (pintype "passive"))
    )
    (net (code "74") (name "Net-(L5-NEG)") (class "Default")
      (node (ref "L5") (pin "1") (pinfunction "NEG_1") (pintype "passive"))
      (node (ref "R11") (pin "1") (pinfunction "1_1") (pintype "passive"))
    )
    (net (code "75") (name "Net-(L5-POS)") (class "Default")
      (node (ref "L5") (pin "2") (pinfunction "POS_2") (pintype "passive"))
      (node (ref "Q3") (pin "1") (pinfunction "BASE_1") (pintype "passive"))
    )
    (net (code "76") (name "Net-(L6-NEG)") (class "Default")
      (node (ref "L6") (pin "1") (pinfunction "NEG_1") (pintype "passive"))
      (node (ref "R12") (pin "1") (pinfunction "1_1") (pintype "passive"))
    )
    (net (code "77") (name "Net-(L6-POS)") (class "Default")
      (node (ref "L6") (pin "2") (pinfunction "POS_2") (pintype "passive"))
      (node (ref "Q4") (pin "1") (pinfunction "BASE_1") (pintype "passive"))
    )
    (net (code "78") (name "Net-(L7-NEG)") (class "Default")
      (node (ref "L7") (pin "1") (pinfunction "NEG_1") (pintype "passive"))
      (node (ref "U7") (pin "3") (pinfunction "E_3") (pintype "passive"))
    )
    (net (code "79") (name "Net-(L8-NEG)") (class "Default")
      (node (ref "L8") (pin "1") (pinfunction "NEG_1") (pintype "passive"))
      (node (ref "U8") (pin "3") (pinfunction "E_3") (pintype "passive"))
    )
    (net (code "80") (name "Net-(L9-NEG)") (class "Default")
      (node (ref "L9") (pin "1") (pinfunction "NEG_1") (pintype "passive"))
      (node (ref "R21") (pin "1") (pinfunction "1_1") (pintype "passive"))
    )
    (net (code "81") (name "Net-(L9-POS)") (class "Default")
      (node (ref "L9") (pin "2") (pinfunction "POS_2") (pintype "passive"))
      (node (ref "Q5") (pin "1") (pinfunction "BASE_1") (pintype "passive"))
    )
    (net (code "82") (name "Net-(L10-NEG)") (class "Default")
      (node (ref "L10") (pin "1") (pinfunction "NEG_1") (pintype "passive"))
      (node (ref "R22") (pin "1") (pinfunction "1_1") (pintype "passive"))
    )
    (net (code "83") (name "Net-(L10-POS)") (class "Default")
      (node (ref "L10") (pin "2") (pinfunction "POS_2") (pintype "passive"))
      (node (ref "Q6") (pin "1") (pinfunction "BASE_1") (pintype "passive"))
    )
    (net (code "84") (name "Net-(L11-NEG)") (class "Default")
      (node (ref "L11") (pin "1") (pinfunction "NEG_1") (pintype "passive"))
      (node (ref "U11") (pin "3") (pinfunction "E_3") (pintype "passive"))
    )
    (net (code "85") (name "Net-(L12-NEG)") (class "Default")
      (node (ref "L12") (pin "1") (pinfunction "NEG_1") (pintype "passive"))
      (node (ref "U12") (pin "3") (pinfunction "E_3") (pintype "passive"))
    )
    (net (code "86") (name "Net-(L13-NEG)") (class "Default")
      (node (ref "L13") (pin "1") (pinfunction "NEG_1") (pintype "passive"))
      (node (ref "R29") (pin "1") (pinfunction "1_1") (pintype "passive"))
    )
    (net (code "87") (name "Net-(L13-POS)") (class "Default")
      (node (ref "L13") (pin "2") (pinfunction "POS_2") (pintype "passive"))
      (node (ref "Q7") (pin "1") (pinfunction "BASE_1") (pintype "passive"))
    )
    (net (code "88") (name "Net-(L14-NEG)") (class "Default")
      (node (ref "L14") (pin "1") (pinfunction "NEG_1") (pintype "passive"))
      (node (ref "R30") (pin "1") (pinfunction "1_1") (pintype "passive"))
    )
    (net (code "89") (name "Net-(L14-POS)") (class "Default")
      (node (ref "L14") (pin "2") (pinfunction "POS_2") (pintype "passive"))
      (node (ref "Q8") (pin "1") (pinfunction "BASE_1") (pintype "passive"))
    )
    (net (code "90") (name "Net-(L15-NEG)") (class "Default")
      (node (ref "L15") (pin "1") (pinfunction "NEG_1") (pintype "passive"))
      (node (ref "U15") (pin "3") (pinfunction "E_3") (pintype "passive"))
    )
    (net (code "91") (name "Net-(L16-NEG)") (class "Default")
      (node (ref "L16") (pin "1") (pinfunction "NEG_1") (pintype "passive"))
      (node (ref "U16") (pin "3") (pinfunction "E_3") (pintype "passive"))
    )
    (net (code "92") (name "Net-(L17-NEG)") (class "Default")
      (node (ref "L17") (pin "1") (pinfunction "NEG_1") (pintype "passive"))
      (node (ref "R37") (pin "1") (pinfunction "1_1") (pintype "passive"))
    )
    (net (code "93") (name "Net-(L17-POS)") (class "Default")
      (node (ref "L17") (pin "2") (pinfunction "POS_2") (pintype "passive"))
      (node (ref "Q9") (pin "1") (pinfunction "BASE_1") (pintype "passive"))
    )
    (net (code "94") (name "Net-(L18-NEG)") (class "Default")
      (node (ref "L18") (pin "1") (pinfunction "NEG_1") (pintype "passive"))
      (node (ref "R38") (pin "1") (pinfunction "1_1") (pintype "passive"))
    )
    (net (code "95") (name "Net-(L18-POS)") (class "Default")
      (node (ref "L18") (pin "2") (pinfunction "POS_2") (pintype "passive"))
      (node (ref "Q10") (pin "1") (pinfunction "BASE_1") (pintype "passive"))
    )
    (net (code "96") (name "Net-(L19-NEG)") (class "Default")
      (node (ref "L19") (pin "1") (pinfunction "NEG_1") (pintype "passive"))
      (node (ref "U19") (pin "3") (pinfunction "E_3") (pintype "passive"))
    )
    (net (code "97") (name "Net-(L20-NEG)") (class "Default")
      (node (ref "L20") (pin "1") (pinfunction "NEG_1") (pintype "passive"))
      (node (ref "U20") (pin "3") (pinfunction "E_3") (pintype "passive"))
    )
    (net (code "98") (name "Net-(L21-NEG)") (class "Default")
      (node (ref "L21") (pin "1") (pinfunction "NEG_1") (pintype "passive"))
      (node (ref "U21") (pin "3") (pinfunction "E_3") (pintype "passive"))
    )
    (net (code "99") (name "Net-(L22-NEG)") (class "Default")
      (node (ref "L22") (pin "1") (pinfunction "NEG_1") (pintype "passive"))
      (node (ref "U22") (pin "3") (pinfunction "E_3") (pintype "passive"))
    )
    (net (code "100") (name "Net-(L23-NEG)") (class "Default")
      (node (ref "L23") (pin "1") (pinfunction "NEG_1") (pintype "passive"))
      (node (ref "R47") (pin "1") (pinfunction "1_1") (pintype "passive"))
    )
    (net (code "101") (name "Net-(L23-POS)") (class "Default")
      (node (ref "L23") (pin "2") (pinfunction "POS_2") (pintype "passive"))
      (node (ref "Q11") (pin "1") (pinfunction "BASE_1") (pintype "passive"))
    )
    (net (code "102") (name "Net-(L24-NEG)") (class "Default")
      (node (ref "L24") (pin "1") (pinfunction "NEG_1") (pintype "passive"))
      (node (ref "R48") (pin "1") (pinfunction "1_1") (pintype "passive"))
    )
    (net (code "103") (name "Net-(L24-POS)") (class "Default")
      (node (ref "L24") (pin "2") (pinfunction "POS_2") (pintype "passive"))
      (node (ref "Q12") (pin "1") (pinfunction "BASE_1") (pintype "passive"))
    )
    (net (code "104") (name "Net-(L25-NEG)") (class "Default")
      (node (ref "L25") (pin "1") (pinfunction "NEG_1") (pintype "passive"))
      (node (ref "U25") (pin "3") (pinfunction "E_3") (pintype "passive"))
    )
    (net (code "105") (name "Net-(L26-NEG)") (class "Default")
      (node (ref "L26") (pin "1") (pinfunction "NEG_1") (pintype "passive"))
      (node (ref "U26") (pin "3") (pinfunction "E_3") (pintype "passive"))
    )
    (net (code "106") (name "Net-(L27-NEG)") (class "Default")
      (node (ref "L27") (pin "1") (pinfunction "NEG_1") (pintype "passive"))
      (node (ref "R55") (pin "1") (pinfunction "1_1") (pintype "passive"))
    )
    (net (code "107") (name "Net-(L27-POS)") (class "Default")
      (node (ref "L27") (pin "2") (pinfunction "POS_2") (pintype "passive"))
      (node (ref "Q13") (pin "1") (pinfunction "BASE_1") (pintype "passive"))
    )
    (net (code "108") (name "Net-(L28-NEG)") (class "Default")
      (node (ref "L28") (pin "1") (pinfunction "NEG_1") (pintype "passive"))
      (node (ref "R56") (pin "1") (pinfunction "1_1") (pintype "passive"))
    )
    (net (code "109") (name "Net-(L28-POS)") (class "Default")
      (node (ref "L28") (pin "2") (pinfunction "POS_2") (pintype "passive"))
      (node (ref "Q14") (pin "1") (pinfunction "BASE_1") (pintype "passive"))
    )
    (net (code "110") (name "Net-(L29-NEG)") (class "Default")
      (node (ref "L29") (pin "1") (pinfunction "NEG_1") (pintype "passive"))
      (node (ref "U29") (pin "3") (pinfunction "E_3") (pintype "passive"))
    )
    (net (code "111") (name "Net-(L30-NEG)") (class "Default")
      (node (ref "L30") (pin "1") (pinfunction "NEG_1") (pintype "passive"))
      (node (ref "U30") (pin "3") (pinfunction "E_3") (pintype "passive"))
    )
    (net (code "112") (name "Net-(L31-NEG)") (class "Default")
      (node (ref "L31") (pin "1") (pinfunction "NEG_1") (pintype "passive"))
      (node (ref "R63") (pin "1") (pinfunction "1_1") (pintype "passive"))
    )
    (net (code "113") (name "Net-(L31-POS)") (class "Default")
      (node (ref "L31") (pin "2") (pinfunction "POS_2") (pintype "passive"))
      (node (ref "Q15") (pin "1") (pinfunction "BASE_1") (pintype "passive"))
    )
    (net (code "114") (name "Net-(L32-NEG)") (class "Default")
      (node (ref "L32") (pin "1") (pinfunction "NEG_1") (pintype "passive"))
      (node (ref "R64") (pin "1") (pinfunction "1_1") (pintype "passive"))
    )
    (net (code "115") (name "Net-(L32-POS)") (class "Default")
      (node (ref "L32") (pin "2") (pinfunction "POS_2") (pintype "passive"))
      (node (ref "Q16") (pin "1") (pinfunction "BASE_1") (pintype "passive"))
    )
    (net (code "116") (name "Net-(U1-A)") (class "Default")
      (node (ref "R1") (pin "1") (pinfunction "1_1") (pintype "passive"))
      (node (ref "U1") (pin "1") (pinfunction "A_1") (pintype "passive"))
    )
    (net (code "117") (name "Net-(U1-E)") (class "Default")
      (node (ref "R5") (pin "2") (pinfunction "2_2") (pintype "passive"))
      (node (ref "U1") (pin "3") (pinfunction "E_3") (pintype "passive"))
    )
    (net (code "118") (name "Net-(U2-A)") (class "Default")
      (node (ref "R2") (pin "1") (pinfunction "1_1") (pintype "passive"))
      (node (ref "U2") (pin "1") (pinfunction "A_1") (pintype "passive"))
    )
    (net (code "119") (name "Net-(U2-E)") (class "Default")
      (node (ref "R6") (pin "2") (pinfunction "2_2") (pintype "passive"))
      (node (ref "U2") (pin "3") (pinfunction "E_3") (pintype "passive"))
    )
    (net (code "120") (name "Net-(U3-K)") (class "Default")
      (node (ref "R7") (pin "1") (pinfunction "1_1") (pintype "passive"))
      (node (ref "U3") (pin "2") (pinfunction "K_2") (pintype "passive"))
    )
    (net (code "121") (name "Net-(U4-K)") (class "Default")
      (node (ref "R8") (pin "1") (pinfunction "1_1") (pintype "passive"))
      (node (ref "U4") (pin "2") (pinfunction "K_2") (pintype "passive"))
    )
    (net (code "122") (name "Net-(U5-A)") (class "Default")
      (node (ref "R9") (pin "1") (pinfunction "1_1") (pintype "passive"))
      (node (ref "U5") (pin "1") (pinfunction "A_1") (pintype "passive"))
    )
    (net (code "123") (name "Net-(U5-E)") (class "Default")
      (node (ref "R11") (pin "2") (pinfunction "2_2") (pintype "passive"))
      (node (ref "U5") (pin "3") (pinfunction "E_3") (pintype "passive"))
    )
    (net (code "124") (name "Net-(U6-A)") (class "Default")
      (node (ref "R10") (pin "1") (pinfunction "1_1") (pintype "passive"))
      (node (ref "U6") (pin "1") (pinfunction "A_1") (pintype "passive"))
    )
    (net (code "125") (name "Net-(U6-E)") (class "Default")
      (node (ref "R12") (pin "2") (pinfunction "2_2") (pintype "passive"))
      (node (ref "U6") (pin "3") (pinfunction "E_3") (pintype "passive"))
    )
    (net (code "126") (name "Net-(U7-K)") (class "Default")
      (node (ref "R15") (pin "1") (pinfunction "1_1") (pintype "passive"))
      (node (ref "U7") (pin "2") (pinfunction "K_2") (pintype "passive"))
    )
    (net (code "127") (name "Net-(U8-K)") (class "Default")
      (node (ref "R16") (pin "1") (pinfunction "1_1") (pintype "passive"))
      (node (ref "U8") (pin "2") (pinfunction "K_2") (pintype "passive"))
    )
    (net (code "128") (name "Net-(U9-A)") (class "Default")
      (node (ref "R17") (pin "1") (pinfunction "1_1") (pintype "passive"))
      (node (ref "U9") (pin "1") (pinfunction "A_1") (pintype "passive"))
    )
    (net (code "129") (name "Net-(U9-E)") (class "Default")
      (node (ref "R21") (pin "2") (pinfunction "2_2") (pintype "passive"))
      (node (ref "U9") (pin "3") (pinfunction "E_3") (pintype "passive"))
    )
    (net (code "130") (name "Net-(U10-A)") (class "Default")
      (node (ref "R18") (pin "1") (pinfunction "1_1") (pintype "passive"))
      (node (ref "U10") (pin "1") (pinfunction "A_1") (pintype "passive"))
    )
    (net (code "131") (name "Net-(U10-E)") (class "Default")
      (node (ref "R22") (pin "2") (pinfunction "2_2") (pintype "passive"))
      (node (ref "U10") (pin "3") (pinfunction "E_3") (pintype "passive"))
    )
    (net (code "132") (name "Net-(U11-K)") (class "Default")
      (node (ref "R23") (pin "1") (pinfunction "1_1") (pintype "passive"))
      (node (ref "U11") (pin "2") (pinfunction "K_2") (pintype "passive"))
    )
    (net (code "133") (name "Net-(U12-K)") (class "Default")
      (node (ref "R24") (pin "1") (pinfunction "1_1") (pintype "passive"))
      (node (ref "U12") (pin "2") (pinfunction "K_2") (pintype "passive"))
    )
    (net (code "134") (name "Net-(U13-A)") (class "Default")
      (node (ref "R25") (pin "1") (pinfunction "1_1") (pintype "passive"))
      (node (ref "U13") (pin "1") (pinfunction "A_1") (pintype "passive"))
    )
    (net (code "135") (name "Net-(U13-E)") (class "Default")
      (node (ref "R29") (pin "2") (pinfunction "2_2") (pintype "passive"))
      (node (ref "U13") (pin "3") (pinfunction "E_3") (pintype "passive"))
    )
    (net (code "136") (name "Net-(U14-A)") (class "Default")
      (node (ref "R26") (pin "1") (pinfunction "1_1") (pintype "passive"))
      (node (ref "U14") (pin "1") (pinfunction "A_1") (pintype "passive"))
    )
    (net (code "137") (name "Net-(U14-E)") (class "Default")
      (node (ref "R30") (pin "2") (pinfunction "2_2") (pintype "passive"))
      (node (ref "U14") (pin "3") (pinfunction "E_3") (pintype "passive"))
    )
    (net (code "138") (name "Net-(U15-K)") (class "Default")
      (node (ref "R31") (pin "1") (pinfunction "1_1") (pintype "passive"))
      (node (ref "U15") (pin "2") (pinfunction "K_2") (pintype "passive"))
    )
    (net (code "139") (name "Net-(U16-K)") (class "Default")
      (node (ref "R32") (pin "1") (pinfunction "1_1") (pintype "passive"))
      (node (ref "U16") (pin "2") (pinfunction "K_2") (pintype "passive"))
    )
    (net (code "140") (name "Net-(U17-A)") (class "Default")
      (node (ref "R35") (pin "1") (pinfunction "1_1") (pintype "passive"))
      (node (ref "U17") (pin "1") (pinfunction "A_1") (pintype "passive"))
    )
    (net (code "141") (name "Net-(U17-E)") (class "Default")
      (node (ref "R37") (pin "2") (pinfunction "2_2") (pintype "passive"))
      (node (ref "U17") (pin "3") (pinfunction "E_3") (pintype "passive"))
    )
    (net (code "142") (name "Net-(U18-A)") (class "Default")
      (node (ref "R36") (pin "1") (pinfunction "1_1") (pintype "passive"))
      (node (ref "U18") (pin "1") (pinfunction "A_1") (pintype "passive"))
    )
    (net (code "143") (name "Net-(U18-E)") (class "Default")
      (node (ref "R38") (pin "2") (pinfunction "2_2") (pintype "passive"))
      (node (ref "U18") (pin "3") (pinfunction "E_3") (pintype "passive"))
    )
    (net (code "144") (name "Net-(U19-K)") (class "Default")
      (node (ref "R39") (pin "1") (pinfunction "1_1") (pintype "passive"))
      (node (ref "U19") (pin "2") (pinfunction "K_2") (pintype "passive"))
    )
    (net (code "145") (name "Net-(U20-K)") (class "Default")
      (node (ref "R40") (pin "1") (pinfunction "1_1") (pintype "passive"))
      (node (ref "U20") (pin "2") (pinfunction "K_2") (pintype "passive"))
    )
    (net (code "146") (name "Net-(U21-K)") (class "Default")
      (node (ref "R45") (pin "1") (pinfunction "1_1") (pintype "passive"))
      (node (ref "U21") (pin "2") (pinfunction "K_2") (pintype "passive"))
    )
    (net (code "147") (name "Net-(U22-K)") (class "Default")
      (node (ref "R46") (pin "1") (pinfunction "1_1") (pintype "passive"))
      (node (ref "U22") (pin "2") (pinfunction "K_2") (pintype "passive"))
    )
    (net (code "148") (name "Net-(U23-A)") (class "Default")
      (node (ref "R43") (pin "1") (pinfunction "1_1") (pintype "passive"))
      (node (ref "U23") (pin "1") (pinfunction "A_1") (pintype "passive"))
    )
    (net (code "149") (name "Net-(U23-E)") (class "Default")
      (node (ref "R47") (pin "2") (pinfunction "2_2") (pintype "passive"))
      (node (ref "U23") (pin "3") (pinfunction "E_3") (pintype "passive"))
    )
    (net (code "150") (name "Net-(U24-A)") (class "Default")
      (node (ref "R44") (pin "1") (pinfunction "1_1") (pintype "passive"))
      (node (ref "U24") (pin "1") (pinfunction "A_1") (pintype "passive"))
    )
    (net (code "151") (name "Net-(U24-E)") (class "Default")
      (node (ref "R48") (pin "2") (pinfunction "2_2") (pintype "passive"))
      (node (ref "U24") (pin "3") (pinfunction "E_3") (pintype "passive"))
    )
    (net (code "152") (name "Net-(U25-K)") (class "Default")
      (node (ref "R53") (pin "1") (pinfunction "1_1") (pintype "passive"))
      (node (ref "U25") (pin "2") (pinfunction "K_2") (pintype "passive"))
    )
    (net (code "153") (name "Net-(U26-K)") (class "Default")
      (node (ref "R54") (pin "1") (pinfunction "1_1") (pintype "passive"))
      (node (ref "U26") (pin "2") (pinfunction "K_2") (pintype "passive"))
    )
    (net (code "154") (name "Net-(U27-A)") (class "Default")
      (node (ref "R51") (pin "1") (pinfunction "1_1") (pintype "passive"))
      (node (ref "U27") (pin "1") (pinfunction "A_1") (pintype "passive"))
    )
    (net (code "155") (name "Net-(U27-E)") (class "Default")
      (node (ref "R55") (pin "2") (pinfunction "2_2") (pintype "passive"))
      (node (ref "U27") (pin "3") (pinfunction "E_3") (pintype "passive"))
    )
    (net (code "156") (name "Net-(U28-A)") (class "Default")
      (node (ref "R52") (pin "1") (pinfunction "1_1") (pintype "passive"))
      (node (ref "U28") (pin "1") (pinfunction "A_1") (pintype "passive"))
    )
    (net (code "157") (name "Net-(U28-E)") (class "Default")
      (node (ref "R56") (pin "2") (pinfunction "2_2") (pintype "passive"))
      (node (ref "U28") (pin "3") (pinfunction "E_3") (pintype "passive"))
    )
    (net (code "158") (name "Net-(U29-K)") (class "Default")
      (node (ref "R61") (pin "1") (pinfunction "1_1") (pintype "passive"))
      (node (ref "U29") (pin "2") (pinfunction "K_2") (pintype "passive"))
    )
    (net (code "159") (name "Net-(U30-K)") (class "Default")
      (node (ref "R62") (pin "1") (pinfunction "1_1") (pintype "passive"))
      (node (ref "U30") (pin "2") (pinfunction "K_2") (pintype "passive"))
    )
    (net (code "160") (name "Net-(U31-A)") (class "Default")
      (node (ref "R59") (pin "1") (pinfunction "1_1") (pintype "passive"))
      (node (ref "U31") (pin "1") (pinfunction "A_1") (pintype "passive"))
    )
    (net (code "161") (name "Net-(U31-E)") (class "Default")
      (node (ref "R63") (pin "2") (pinfunction "2_2") (pintype "passive"))
      (node (ref "U31") (pin "3") (pinfunction "E_3") (pintype "passive"))
    )
    (net (code "162") (name "Net-(U32-A)") (class "Default")
      (node (ref "R60") (pin "1") (pinfunction "1_1") (pintype "passive"))
      (node (ref "U32") (pin "1") (pinfunction "A_1") (pintype "passive"))
    )
    (net (code "163") (name "Net-(U32-E)") (class "Default")
      (node (ref "R64") (pin "2") (pinfunction "2_2") (pintype "passive"))
      (node (ref "U32") (pin "3") (pinfunction "E_3") (pintype "passive"))
    )
  )
)
